# MicroMultimeter_LED_Sch.net
KiCad netlist of a schematic drawn in Altium Designer
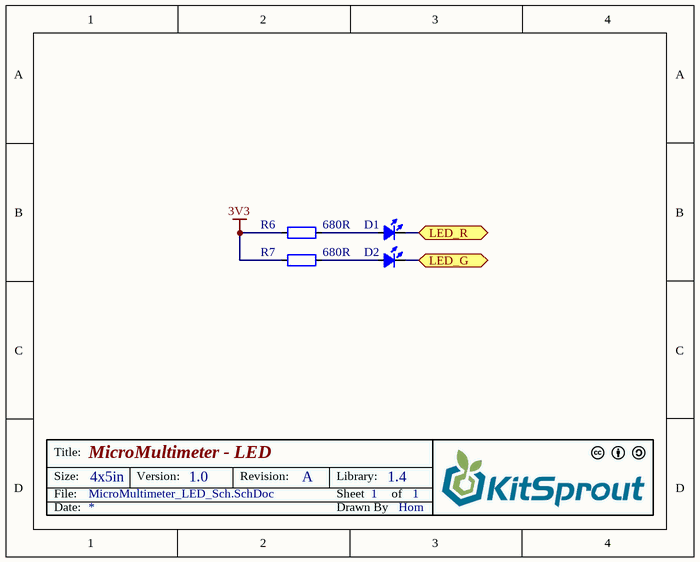
[diagram p0: MicroMultimeter_LED_Sch.SchDoc]

(export (version "E")
  (design (tool "Eeschema 10.0.6"))
  (components
    (comp (ref "D1")
      (value "LED_0603")
      (footprint "PCB_ActiveLED:LED_0603_RED")
      (description "LED")
      (libsource (lib "SCH_Active") (part "LED_0603"))
    )
    (comp (ref "D2")
      (value "LED_0603")
      (footprint "PCB_ActiveLED:LED_0603_GREEN")
      (description "LED")
      (libsource (lib "SCH_Active") (part "LED_0603"))
    )
    (comp (ref "R6")
      (value "680R")
      (footprint "RES_0603")
      (description "Resistor")
      (fields (field (name "Comment") "Res_0603"))
      (libsource (lib "SCH_Passive") (part "Res_0603"))
    )
    (comp (ref "R7")
      (value "680R")
      (footprint "RES_0603")
      (description "Resistor")
      (fields (field (name "Comment") "Res_0603"))
      (libsource (lib "SCH_Passive") (part "Res_0603"))
    )
  )
  (nets
    (net (code "1") (name "/LED_G") (class "Default")
      (node (ref "D2") (pin "2") (pinfunction "K_2") (pintype "passive"))
    )
    (net (code "2") (name "/LED_R") (class "Default")
      (node (ref "D1") (pin "2") (pinfunction "K_2") (pintype "passive"))
    )
    (net (code "3") (name "3V3") (class "Default")
      (node (ref "R6") (pin "2") (pinfunction "2_2") (pintype "passive"))
      (node (ref "R7") (pin "2") (pinfunction "2_2") (pintype "passive"))
    )
    (net (code "4") (name "Net-(D1-A)") (class "Default")
      (node (ref "D1") (pin "1") (pinfunction "A_1") (pintype "passive"))
      (node (ref "R6") (pin "1") (pinfunction "1_1") (pintype "passive"))
    )
    (net (code "5") (name "Net-(D2-A)") (class "Default")
      (node (ref "D2") (pin "1") (pinfunction "A_1") (pintype "passive"))
      (node (ref "R7") (pin "1") (pinfunction "1_1") (pintype "passive"))
    )
  )
)
